# Fuente_Alimentacion.net
KiCad netlist of a schematic drawn in Altium Designer
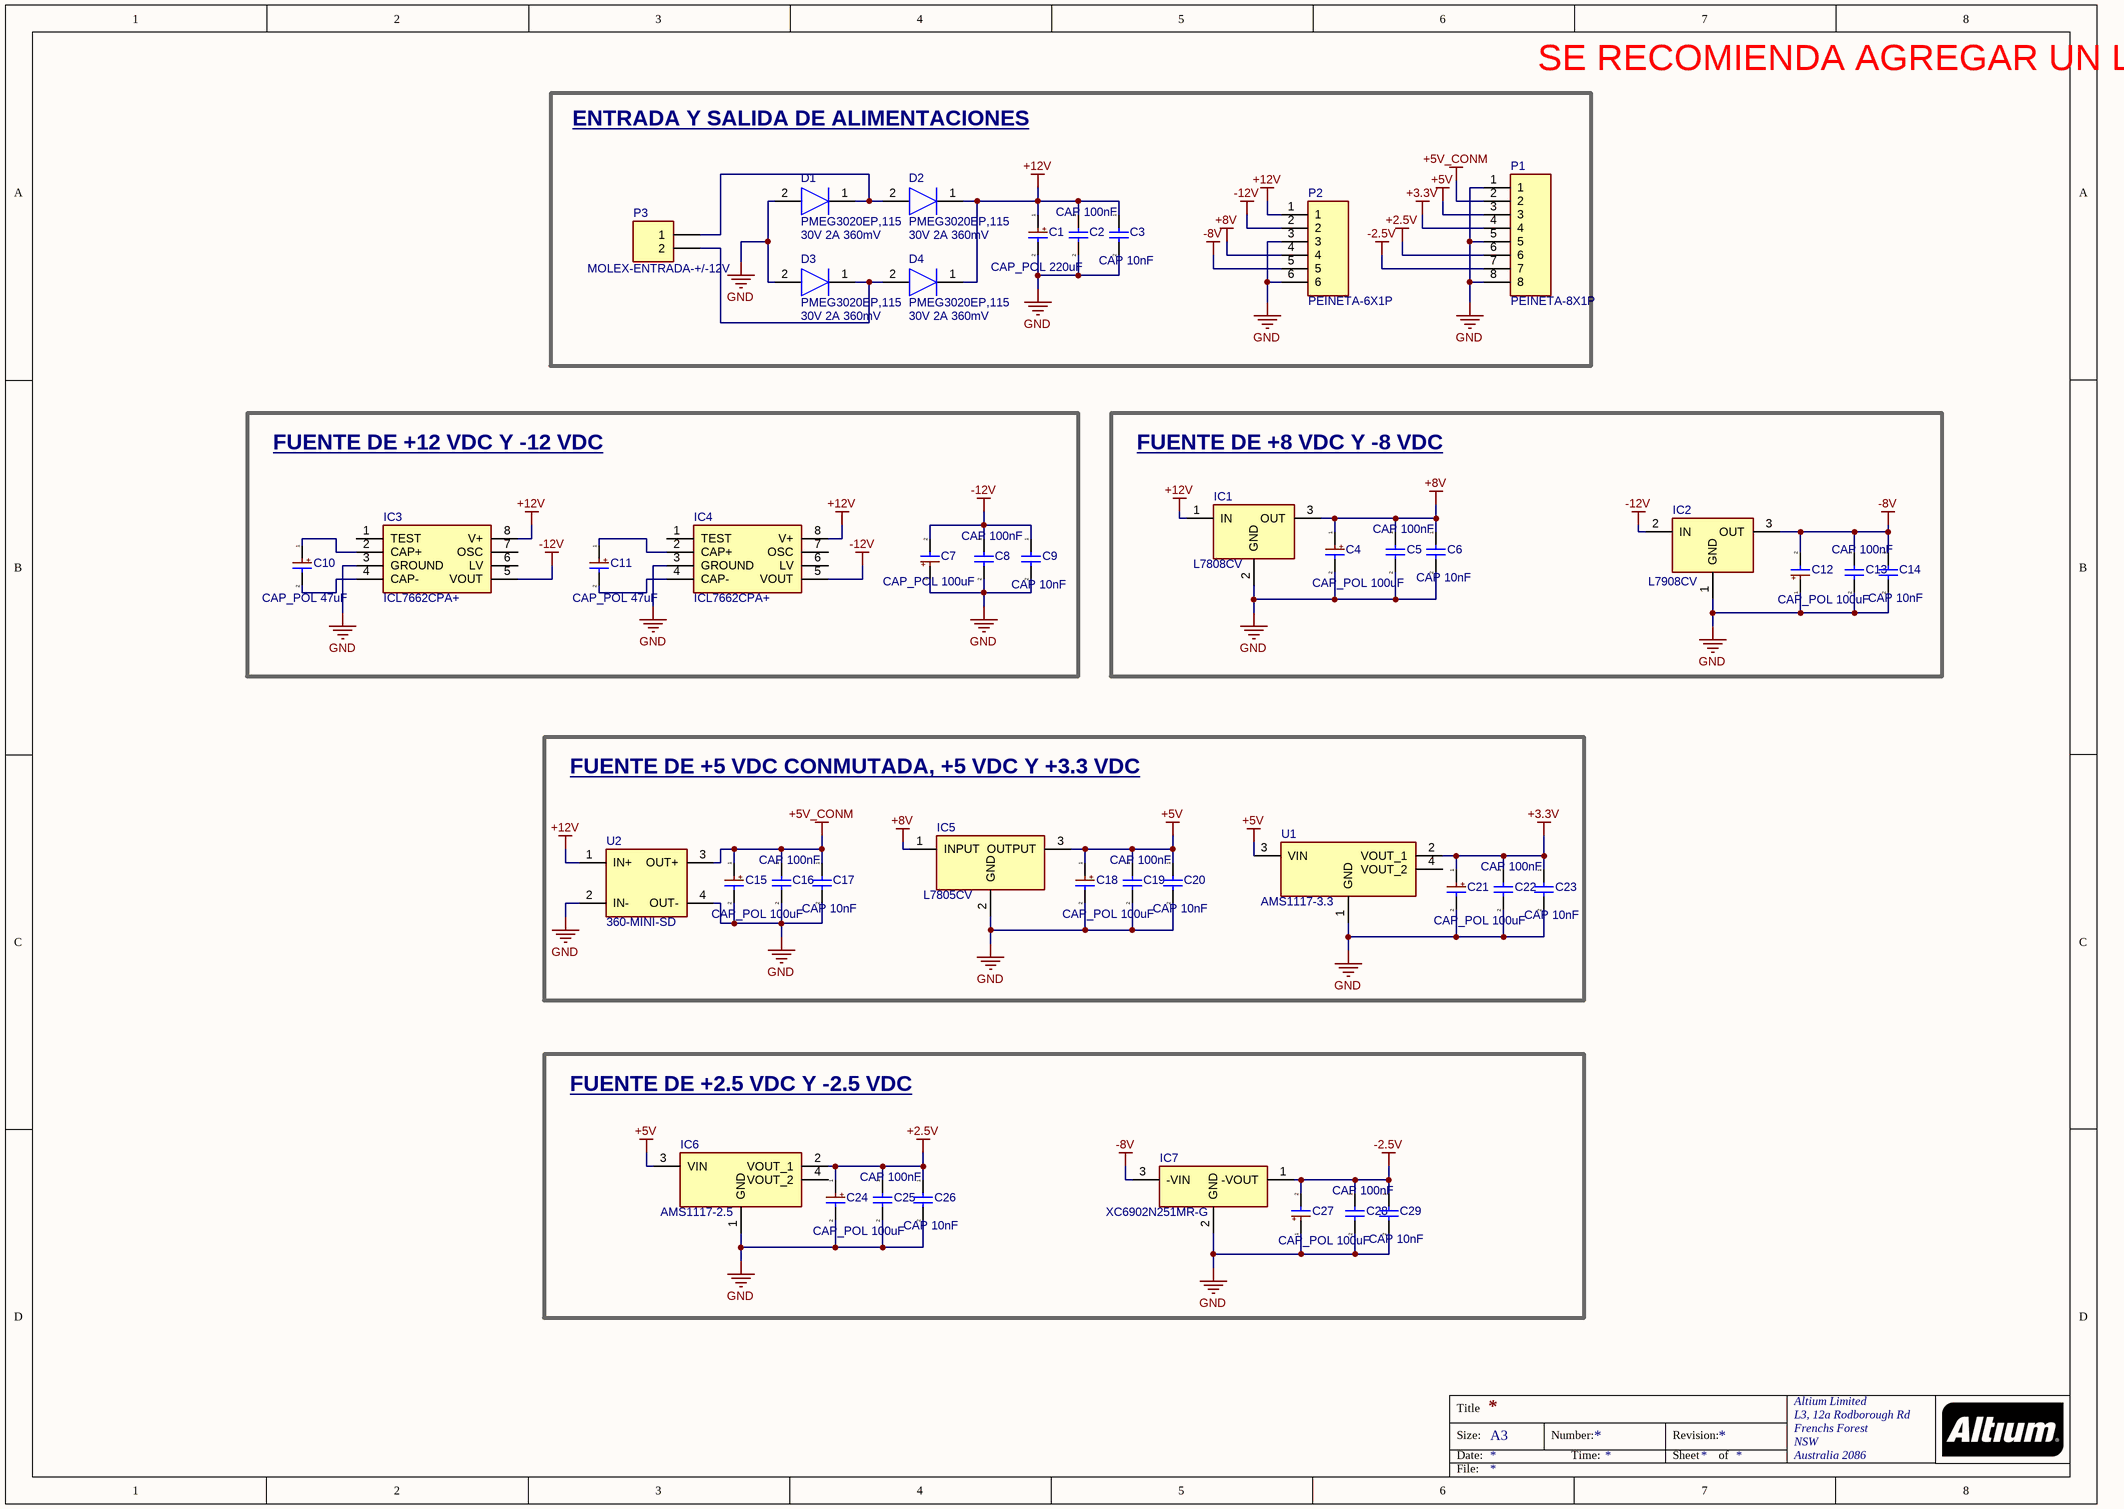
[diagram p0: Fuente_Alimentacion.SchDoc]

(export (version "E")
  (design (tool "Eeschema 10.0.6"))
  (components
    (comp (ref "C1")
      (value "CAP_POL 220uF")
      (footprint "CAP-2.5-6.3MM")
      (description "Basicos")
      (libsource (lib "AltiumLL") (part "CAP_POL"))
    )
    (comp (ref "C2")
      (value "CAP 100nF")
      (footprint "RADIAL-0.1")
      (description "Basicos")
      (libsource (lib "AltiumLL") (part "CAP"))
    )
    (comp (ref "C3")
      (value "CAP 10nF")
      (footprint "RADIAL-0.1")
      (description "Basicos")
      (libsource (lib "AltiumLL") (part "CAP"))
    )
    (comp (ref "C4")
      (value "CAP_POL 100uF")
      (footprint "CAP-2.0-5.0MM")
      (description "Basicos")
      (libsource (lib "AltiumLL") (part "CAP_POL"))
    )
    (comp (ref "C5")
      (value "CAP 100nF")
      (footprint "RADIAL-0.1")
      (description "Basicos")
      (libsource (lib "AltiumLL") (part "CAP"))
    )
    (comp (ref "C6")
      (value "CAP 10nF")
      (footprint "RADIAL-0.1")
      (description "Basicos")
      (libsource (lib "AltiumLL") (part "CAP"))
    )
    (comp (ref "C7")
      (value "CAP_POL 100uF")
      (footprint "CAP-2.0-5.0MM")
      (description "Basicos")
      (libsource (lib "AltiumLL") (part "CAP_POL"))
    )
    (comp (ref "C8")
      (value "CAP 100nF")
      (footprint "RADIAL-0.1")
      (description "Basicos")
      (libsource (lib "AltiumLL") (part "CAP"))
    )
    (comp (ref "C9")
      (value "CAP 10nF")
      (footprint "RADIAL-0.1")
      (description "Basicos")
      (libsource (lib "AltiumLL") (part "CAP"))
    )
    (comp (ref "C10")
      (value "CAP_POL 47uF")
      (footprint "CAP-2.0-5.0MM")
      (description "Basicos")
      (libsource (lib "AltiumLL") (part "CAP_POL"))
    )
    (comp (ref "C11")
      (value "CAP_POL 47uF")
      (footprint "CAP-2.0-5.0MM")
      (description "Basicos")
      (libsource (lib "AltiumLL") (part "CAP_POL"))
    )
    (comp (ref "C12")
      (value "CAP_POL 100uF")
      (footprint "CAP-2.0-5.0MM")
      (description "Basicos")
      (libsource (lib "AltiumLL") (part "CAP_POL"))
    )
    (comp (ref "C13")
      (value "CAP 100nF")
      (footprint "RADIAL-0.1")
      (description "Basicos")
      (libsource (lib "AltiumLL") (part "CAP"))
    )
    (comp (ref "C14")
      (value "CAP 10nF")
      (footprint "RADIAL-0.1")
      (description "Basicos")
      (libsource (lib "AltiumLL") (part "CAP"))
    )
    (comp (ref "C15")
      (value "CAP_POL 100uF")
      (footprint "CAP-2.0-5.0MM")
      (description "Basicos")
      (libsource (lib "AltiumLL") (part "CAP_POL"))
    )
    (comp (ref "C16")
      (value "CAP 100nF")
      (footprint "RADIAL-0.1")
      (description "Basicos")
      (libsource (lib "AltiumLL") (part "CAP"))
    )
    (comp (ref "C17")
      (value "CAP 10nF")
      (footprint "RADIAL-0.1")
      (description "Basicos")
      (libsource (lib "AltiumLL") (part "CAP"))
    )
    (comp (ref "C18")
      (value "CAP_POL 100uF")
      (footprint "CAP-2.0-5.0MM")
      (description "Basicos")
      (libsource (lib "AltiumLL") (part "CAP_POL"))
    )
    (comp (ref "C19")
      (value "CAP 100nF")
      (footprint "RADIAL-0.1")
      (description "Basicos")
      (libsource (lib "AltiumLL") (part "CAP"))
    )
    (comp (ref "C20")
      (value "CAP 10nF")
      (footprint "RADIAL-0.1")
      (description "Basicos")
      (libsource (lib "AltiumLL") (part "CAP"))
    )
    (comp (ref "C21")
      (value "CAP_POL 100uF")
      (footprint "CAP-2.0-5.0MM")
      (description "Basicos")
      (libsource (lib "AltiumLL") (part "CAP_POL"))
    )
    (comp (ref "C22")
      (value "CAP 100nF")
      (footprint "RADIAL-0.1")
      (description "Basicos")
      (libsource (lib "AltiumLL") (part "CAP"))
    )
    (comp (ref "C23")
      (value "CAP 10nF")
      (footprint "RADIAL-0.1")
      (description "Basicos")
      (libsource (lib "AltiumLL") (part "CAP"))
    )
    (comp (ref "C24")
      (value "CAP_POL 100uF")
      (footprint "CAP-2.0-5.0MM")
      (description "Basicos")
      (libsource (lib "AltiumLL") (part "CAP_POL"))
    )
    (comp (ref "C25")
      (value "CAP 100nF")
      (footprint "RADIAL-0.1")
      (description "Basicos")
      (libsource (lib "AltiumLL") (part "CAP"))
    )
    (comp (ref "C26")
      (value "CAP 10nF")
      (footprint "RADIAL-0.1")
      (description "Basicos")
      (libsource (lib "AltiumLL") (part "CAP"))
    )
    (comp (ref "C27")
      (value "CAP_POL 100uF")
      (footprint "CAP-2.0-5.0MM")
      (description "Basicos")
      (libsource (lib "AltiumLL") (part "CAP_POL"))
    )
    (comp (ref "C28")
      (value "CAP 100nF")
      (footprint "RADIAL-0.1")
      (description "Basicos")
      (libsource (lib "AltiumLL") (part "CAP"))
    )
    (comp (ref "C29")
      (value "CAP 10nF")
      (footprint "RADIAL-0.1")
      (description "Basicos")
      (libsource (lib "AltiumLL") (part "CAP"))
    )
    (comp (ref "D1")
      (value "PMEG3020EP,115")
      (footprint "SODFL4725X110N")
      (description "Diode")
      (fields
        (field (name "MOUSER PART NUMBER") "771-PMEG3020EP115")
        (field (name "JLCPCB PART #") "C513108")
        (field (name "ALTIUM_VALUE") "30V 2A 360mV")
      )
      (libsource (lib "AltiumLL") (part "PMEG3020EP,115"))
    )
    (comp (ref "D2")
      (value "PMEG3020EP,115")
      (footprint "SODFL4725X110N")
      (description "Diode")
      (fields
        (field (name "MOUSER PART NUMBER") "771-PMEG3020EP115")
        (field (name "JLCPCB PART #") "C513108")
        (field (name "ALTIUM_VALUE") "30V 2A 360mV")
      )
      (libsource (lib "AltiumLL") (part "PMEG3020EP,115"))
    )
    (comp (ref "D3")
      (value "PMEG3020EP,115")
      (footprint "SODFL4725X110N")
      (description "Diode")
      (fields
        (field (name "MOUSER PART NUMBER") "771-PMEG3020EP115")
        (field (name "JLCPCB PART #") "C513108")
        (field (name "ALTIUM_VALUE") "30V 2A 360mV")
      )
      (libsource (lib "AltiumLL") (part "PMEG3020EP,115"))
    )
    (comp (ref "D4")
      (value "PMEG3020EP,115")
      (footprint "SODFL4725X110N")
      (description "Diode")
      (fields
        (field (name "MOUSER PART NUMBER") "771-PMEG3020EP115")
        (field (name "JLCPCB PART #") "C513108")
        (field (name "ALTIUM_VALUE") "30V 2A 360mV")
      )
      (libsource (lib "AltiumLL") (part "PMEG3020EP,115"))
    )
    (comp (ref "IC1")
      (value "L7808CV")
      (footprint "TO270P460X1020X2008-3P")
      (description "Integrated Circuit")
      (fields (field (name "MOUSER PART NUMBER") "511-L7808CV") (field (name "JLCPCB PART #") "C519076"))
      (libsource (lib "AltiumLL") (part "L7808CV"))
    )
    (comp (ref "IC2")
      (value "L7908CV")
      (footprint "TO270P460X1020X2008-3P")
      (description "Integrated Circuit")
      (fields (field (name "MOUSER PART NUMBER") "511-L7908CV") (field (name "JLCPCB PART #") "C26162"))
      (libsource (lib "AltiumLL") (part "L7908CV"))
    )
    (comp (ref "IC3")
      (value "ICL7662CPA+")
      (footprint "DIP794W56P254L938H457Q8N")
      (description "Integrated Circuit")
      (fields (field (name "MOUSER PART NUMBER") "700-ICL7662CPA") (field (name "JLCPCB PART #") "C14340"))
      (libsource (lib "AltiumLL") (part "ICL7662CPA+"))
    )
    (comp (ref "IC4")
      (value "ICL7662CPA+")
      (footprint "DIP794W56P254L938H457Q8N")
      (description "Integrated Circuit")
      (fields (field (name "MOUSER PART NUMBER") "700-ICL7662CPA") (field (name "JLCPCB PART #") "C14340"))
      (libsource (lib "AltiumLL") (part "ICL7662CPA+"))
    )
    (comp (ref "IC5")
      (value "L7805CV")
      (footprint "TO255P460X1020X2008-3P")
      (description "Integrated Circuit")
      (fields (field (name "MOUSER PART NUMBER") "511-L7805CV") (field (name "JLCPCB PART #") "C111887"))
      (libsource (lib "AltiumLL") (part "L7805CV"))
    )
    (comp (ref "IC6")
      (value "AMS1117-2.5")
      (footprint "SOT229P700X180-4N")
      (description "Integrated Circuit")
      (fields (field (name "JLCPCB PART #") "C12087"))
      (libsource (lib "AltiumLL") (part "AMS1117-2.5"))
    )
    (comp (ref "IC7")
      (value "XC6902N251MR-G")
      (footprint "SOT95P280X130-3N")
      (description "Integrated Circuit")
      (fields (field (name "MOUSER PART NUMBER") "865-XC6902N251MR-G"))
      (libsource (lib "AltiumLL") (part "XC6902N251MR-G"))
    )
    (comp (ref "P1")
      (value "PEINETA-8X1P")
      (footprint "SIP-8X1P-M-V")
      (description "Conector")
      (libsource (lib "AltiumLL") (part "PEINETA-8X1P"))
    )
    (comp (ref "P2")
      (value "PEINETA-6X1P")
      (footprint "SIP-6X1P-M-V")
      (description "Conector")
      (libsource (lib "AltiumLL") (part "PEINETA-6X1P"))
    )
    (comp (ref "P3")
      (value "MOLEX-ENTRADA-+/-12V")
      (footprint "MOLEX-2P")
      (description "Conector")
      (libsource (lib "AltiumLL") (part "MOLEX-2P"))
    )
    (comp (ref "U1")
      (value "AMS1117-3.3")
      (footprint "SOT229P700X180-4N")
      (description "Integrated Circuit")
      (fields (field (name "JLCPCB PART #") "C6186"))
      (libsource (lib "AltiumLL") (part "AMS1117-3.3"))
    )
    (comp (ref "U2")
      (value "360-MINI-SD")
      (footprint "360-MINI-SD-v1")
      (description "Basicos")
      (libsource (lib "AltiumLL") (part "360-MINI-SD"))
    )
  )
  (nets
    (net (code "1") (name "+2.5V") (class "Default")
      (node (ref "C24") (pin "1") (pinfunction "-_1") (pintype "passive"))
      (node (ref "C25") (pin "1") (pinfunction "1_1") (pintype "passive"))
      (node (ref "C26") (pin "1") (pinfunction "1_1") (pintype "passive"))
      (node (ref "IC6") (pin "2") (pinfunction "VOUT_1_2") (pintype "passive"))
      (node (ref "P1") (pin "6") (pinfunction "6_6") (pintype "passive"))
    )
    (net (code "2") (name "+3.3V") (class "Default")
      (node (ref "C21") (pin "1") (pinfunction "-_1") (pintype "passive"))
      (node (ref "C22") (pin "1") (pinfunction "1_1") (pintype "passive"))
      (node (ref "C23") (pin "1") (pinfunction "1_1") (pintype "passive"))
      (node (ref "P1") (pin "4") (pinfunction "4_4") (pintype "passive"))
      (node (ref "U1") (pin "2") (pinfunction "VOUT_1_2") (pintype "passive"))
    )
    (net (code "3") (name "+5V") (class "Default")
      (node (ref "C18") (pin "1") (pinfunction "-_1") (pintype "passive"))
      (node (ref "C19") (pin "1") (pinfunction "1_1") (pintype "passive"))
      (node (ref "C20") (pin "1") (pinfunction "1_1") (pintype "passive"))
      (node (ref "IC5") (pin "3") (pinfunction "OUTPUT_3") (pintype "passive"))
      (node (ref "IC6") (pin "3") (pinfunction "VIN_3") (pintype "passive"))
      (node (ref "P1") (pin "3") (pinfunction "3_3") (pintype "passive"))
      (node (ref "U1") (pin "3") (pinfunction "VIN_3") (pintype "passive"))
    )
    (net (code "4") (name "+5V_CONM") (class "Default")
      (node (ref "C15") (pin "1") (pinfunction "-_1") (pintype "passive"))
      (node (ref "C16") (pin "1") (pinfunction "1_1") (pintype "passive"))
      (node (ref "C17") (pin "1") (pinfunction "1_1") (pintype "passive"))
      (node (ref "P1") (pin "2") (pinfunction "2_2") (pintype "passive"))
      (node (ref "U2") (pin "3") (pinfunction "OUT+_3") (pintype "power_in"))
    )
    (net (code "5") (name "+8V") (class "Default")
      (node (ref "C4") (pin "1") (pinfunction "-_1") (pintype "passive"))
      (node (ref "C5") (pin "1") (pinfunction "1_1") (pintype "passive"))
      (node (ref "C6") (pin "1") (pinfunction "1_1") (pintype "passive"))
      (node (ref "IC1") (pin "3") (pinfunction "OUT_3") (pintype "power_in"))
      (node (ref "IC5") (pin "1") (pinfunction "INPUT_1") (pintype "passive"))
      (node (ref "P2") (pin "4") (pinfunction "4_4") (pintype "passive"))
    )
    (net (code "6") (name "+12V") (class "Default")
      (node (ref "C1") (pin "1") (pinfunction "-_1") (pintype "passive"))
      (node (ref "C2") (pin "1") (pinfunction "1_1") (pintype "passive"))
      (node (ref "C3") (pin "1") (pinfunction "1_1") (pintype "passive"))
      (node (ref "D2") (pin "1") (pinfunction "K_1") (pintype "passive"))
      (node (ref "D4") (pin "1") (pinfunction "K_1") (pintype "passive"))
      (node (ref "IC1") (pin "1") (pinfunction "IN_1") (pintype "power_in"))
      (node (ref "IC3") (pin "8") (pinfunction "V+_8") (pintype "passive"))
      (node (ref "IC4") (pin "8") (pinfunction "V+_8") (pintype "passive"))
      (node (ref "P2") (pin "1") (pinfunction "1_1") (pintype "passive"))
      (node (ref "U2") (pin "1") (pinfunction "IN+_1") (pintype "power_in"))
    )
    (net (code "7") (name "-2.5V") (class "Default")
      (node (ref "C27") (pin "2") (pinfunction "+_2") (pintype "passive"))
      (node (ref "C28") (pin "1") (pinfunction "1_1") (pintype "passive"))
      (node (ref "C29") (pin "1") (pinfunction "1_1") (pintype "passive"))
      (node (ref "IC7") (pin "1") (pinfunction "-VOUT_1") (pintype "passive"))
      (node (ref "P1") (pin "7") (pinfunction "7_7") (pintype "passive"))
    )
    (net (code "8") (name "-8V") (class "Default")
      (node (ref "C12") (pin "2") (pinfunction "+_2") (pintype "passive"))
      (node (ref "C13") (pin "1") (pinfunction "1_1") (pintype "passive"))
      (node (ref "C14") (pin "1") (pinfunction "1_1") (pintype "passive"))
      (node (ref "IC2") (pin "3") (pinfunction "OUT_3") (pintype "power_in"))
      (node (ref "IC7") (pin "3") (pinfunction "-VIN_3") (pintype "passive"))
      (node (ref "P2") (pin "5") (pinfunction "5_5") (pintype "passive"))
    )
    (net (code "9") (name "-12V") (class "Default")
      (node (ref "C7") (pin "2") (pinfunction "+_2") (pintype "passive"))
      (node (ref "C8") (pin "1") (pinfunction "1_1") (pintype "passive"))
      (node (ref "C9") (pin "1") (pinfunction "1_1") (pintype "passive"))
      (node (ref "IC2") (pin "2") (pinfunction "IN_2") (pintype "power_in"))
      (node (ref "IC3") (pin "5") (pinfunction "VOUT_5") (pintype "passive"))
      (node (ref "IC4") (pin "5") (pinfunction "VOUT_5") (pintype "passive"))
      (node (ref "P2") (pin "2") (pinfunction "2_2") (pintype "passive"))
    )
    (net (code "10") (name "GND") (class "Default")
      (node (ref "C1") (pin "2") (pinfunction "+_2") (pintype "passive"))
      (node (ref "C12") (pin "1") (pinfunction "-_1") (pintype "passive"))
      (node (ref "C13") (pin "2") (pinfunction "2_2") (pintype "passive"))
      (node (ref "C14") (pin "2") (pinfunction "2_2") (pintype "passive"))
      (node (ref "C15") (pin "2") (pinfunction "+_2") (pintype "passive"))
      (node (ref "C16") (pin "2") (pinfunction "2_2") (pintype "passive"))
      (node (ref "C17") (pin "2") (pinfunction "2_2") (pintype "passive"))
      (node (ref "C18") (pin "2") (pinfunction "+_2") (pintype "passive"))
      (node (ref "C19") (pin "2") (pinfunction "2_2") (pintype "passive"))
      (node (ref "C2") (pin "2") (pinfunction "2_2") (pintype "passive"))
      (node (ref "C20") (pin "2") (pinfunction "2_2") (pintype "passive"))
      (node (ref "C21") (pin "2") (pinfunction "+_2") (pintype "passive"))
      (node (ref "C22") (pin "2") (pinfunction "2_2") (pintype "passive"))
      (node (ref "C23") (pin "2") (pinfunction "2_2") (pintype "passive"))
      (node (ref "C24") (pin "2") (pinfunction "+_2") (pintype "passive"))
      (node (ref "C25") (pin "2") (pinfunction "2_2") (pintype "passive"))
      (node (ref "C26") (pin "2") (pinfunction "2_2") (pintype "passive"))
      (node (ref "C27") (pin "1") (pinfunction "-_1") (pintype "passive"))
      (node (ref "C28") (pin "2") (pinfunction "2_2") (pintype "passive"))
      (node (ref "C29") (pin "2") (pinfunction "2_2") (pintype "passive"))
      (node (ref "C3") (pin "2") (pinfunction "2_2") (pintype "passive"))
      (node (ref "C4") (pin "2") (pinfunction "+_2") (pintype "passive"))
      (node (ref "C5") (pin "2") (pinfunction "2_2") (pintype "passive"))
      (node (ref "C6") (pin "2") (pinfunction "2_2") (pintype "passive"))
      (node (ref "C7") (pin "1") (pinfunction "-_1") (pintype "passive"))
      (node (ref "C8") (pin "2") (pinfunction "2_2") (pintype "passive"))
      (node (ref "C9") (pin "2") (pinfunction "2_2") (pintype "passive"))
      (node (ref "D1") (pin "2") (pinfunction "A_2") (pintype "passive"))
      (node (ref "D3") (pin "2") (pinfunction "A_2") (pintype "passive"))
      (node (ref "IC1") (pin "2") (pinfunction "GND_2") (pintype "power_in"))
      (node (ref "IC2") (pin "1") (pinfunction "GND_1") (pintype "power_in"))
      (node (ref "IC3") (pin "3") (pinfunction "GROUND_3") (pintype "passive"))
      (node (ref "IC4") (pin "3") (pinfunction "GROUND_3") (pintype "passive"))
      (node (ref "IC5") (pin "2") (pinfunction "GND_2") (pintype "passive"))
      (node (ref "IC6") (pin "1") (pinfunction "GND_1") (pintype "passive"))
      (node (ref "IC7") (pin "2") (pinfunction "GND_2") (pintype "passive"))
      (node (ref "P1") (pin "1") (pinfunction "1_1") (pintype "passive"))
      (node (ref "P1") (pin "5") (pinfunction "5_5") (pintype "passive"))
      (node (ref "P1") (pin "8") (pinfunction "8_8") (pintype "passive"))
      (node (ref "P2") (pin "3") (pinfunction "3_3") (pintype "passive"))
      (node (ref "P2") (pin "6") (pinfunction "6_6") (pintype "passive"))
      (node (ref "U1") (pin "1") (pinfunction "GND_1") (pintype "passive"))
      (node (ref "U2") (pin "2") (pinfunction "IN-_2") (pintype "power_in"))
      (node (ref "U2") (pin "4") (pinfunction "OUT-_4") (pintype "power_in"))
    )
    (net (code "11") (name "Net-(C10-+)") (class "Default")
      (node (ref "C10") (pin "2") (pinfunction "+_2") (pintype "passive"))
      (node (ref "IC3") (pin "4") (pinfunction "CAP-_4") (pintype "passive"))
    )
    (net (code "12") (name "Net-(C10--)") (class "Default")
      (node (ref "C10") (pin "1") (pinfunction "-_1") (pintype "passive"))
      (node (ref "IC3") (pin "2") (pinfunction "CAP+_2") (pintype "passive"))
    )
    (net (code "13") (name "Net-(C11-+)") (class "Default")
      (node (ref "C11") (pin "2") (pinfunction "+_2") (pintype "passive"))
      (node (ref "IC4") (pin "4") (pinfunction "CAP-_4") (pintype "passive"))
    )
    (net (code "14") (name "Net-(C11--)") (class "Default")
      (node (ref "C11") (pin "1") (pinfunction "-_1") (pintype "passive"))
      (node (ref "IC4") (pin "2") (pinfunction "CAP+_2") (pintype "passive"))
    )
    (net (code "15") (name "Net-(D1-K)") (class "Default")
      (node (ref "D1") (pin "1") (pinfunction "K_1") (pintype "passive"))
      (node (ref "D2") (pin "2") (pinfunction "A_2") (pintype "passive"))
      (node (ref "P3") (pin "1") (pinfunction "1_1") (pintype "passive"))
    )
    (net (code "16") (name "Net-(D3-K)") (class "Default")
      (node (ref "D3") (pin "1") (pinfunction "K_1") (pintype "passive"))
      (node (ref "D4") (pin "2") (pinfunction "A_2") (pintype "passive"))
      (node (ref "P3") (pin "2") (pinfunction "2_2") (pintype "passive"))
    )
    (net (code "17") (name "unconnected-(IC3-LV-Pad6)") (class "Default")
      (node (ref "IC3") (pin "6") (pinfunction "LV_6") (pintype "passive"))
    )
    (net (code "18") (name "unconnected-(IC3-OSC-Pad7)") (class "Default")
      (node (ref "IC3") (pin "7") (pinfunction "OSC_7") (pintype "passive"))
    )
    (net (code "19") (name "unconnected-(IC3-TEST-Pad1)") (class "Default")
      (node (ref "IC3") (pin "1") (pinfunction "TEST_1") (pintype "passive"))
    )
    (net (code "20") (name "unconnected-(IC4-LV-Pad6)") (class "Default")
      (node (ref "IC4") (pin "6") (pinfunction "LV_6") (pintype "passive"))
    )
    (net (code "21") (name "unconnected-(IC4-OSC-Pad7)") (class "Default")
      (node (ref "IC4") (pin "7") (pinfunction "OSC_7") (pintype "passive"))
    )
    (net (code "22") (name "unconnected-(IC4-TEST-Pad1)") (class "Default")
      (node (ref "IC4") (pin "1") (pinfunction "TEST_1") (pintype "passive"))
    )
    (net (code "23") (name "unconnected-(IC6-VOUT_2-Pad4)") (class "Default")
      (node (ref "IC6") (pin "4") (pinfunction "VOUT_2_4") (pintype "passive"))
    )
    (net (code "24") (name "unconnected-(U1-VOUT_2-Pad4)") (class "Default")
      (node (ref "U1") (pin "4") (pinfunction "VOUT_2_4") (pintype "passive"))
    )
  )
)
